# grizzly_bear_jig.net
KiCad netlist of a schematic drawn in EAGLE
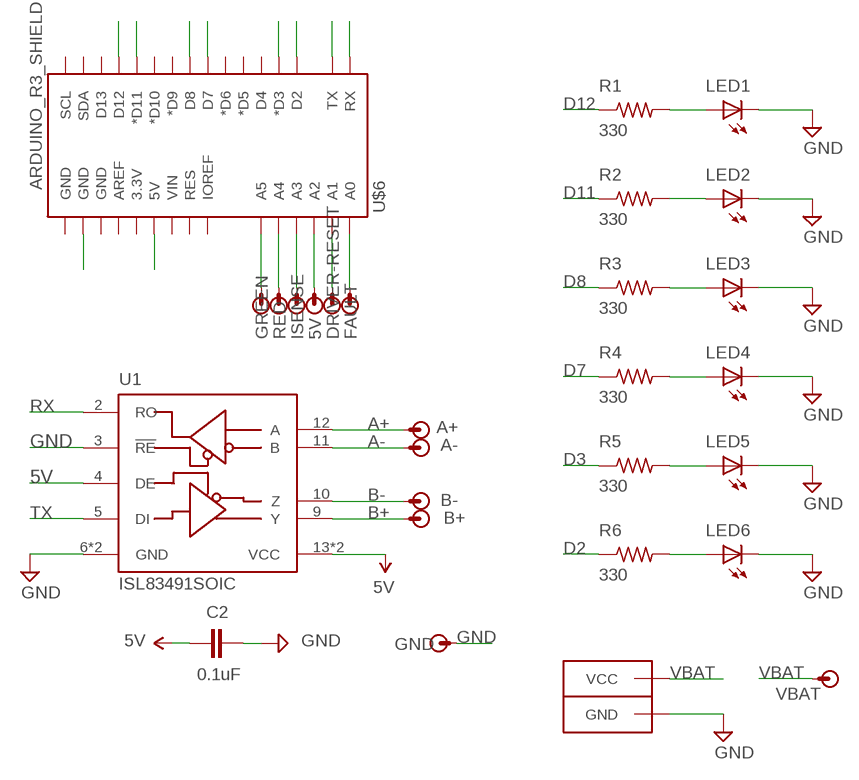
[diagram p0: schematic, sheet 1]

(export (version "E")
  (design (tool "Eeschema 10.0.6"))
  (components
    (comp (ref "5V")
      (value "POGO_PIN")
      (footprint "eagle-import:POGO_PIN_394")
      (libsource (lib "eagle-import") (part "POGO_PIN"))
    )
    (comp (ref "A+")
      (value "POGO_PIN")
      (footprint "eagle-import:POGO_PIN_394")
      (libsource (lib "eagle-import") (part "POGO_PIN"))
    )
    (comp (ref "A-")
      (value "POGO_PIN")
      (footprint "eagle-import:POGO_PIN_394")
      (libsource (lib "eagle-import") (part "POGO_PIN"))
    )
    (comp (ref "B+")
      (value "POGO_PIN")
      (footprint "eagle-import:POGO_PIN_394")
      (libsource (lib "eagle-import") (part "POGO_PIN"))
    )
    (comp (ref "B-")
      (value "POGO_PIN")
      (footprint "eagle-import:POGO_PIN_394")
      (libsource (lib "eagle-import") (part "POGO_PIN"))
    )
    (comp (ref "C2")
      (value "0.1uF")
      (footprint "eagle-import:0603-CAP")
      (libsource (lib "eagle-import") (part "0.1UF-25V(+80/-20%)(0603)"))
    )
    (comp (ref "CONN1")
      (value "ANDERSONHORIZONTAL")
      (footprint "eagle-import:ANDERSON_HORIZONTAL")
      (libsource (lib "eagle-import") (part "ANDERSONHORIZONTAL"))
    )
    (comp (ref "DRIVER-RESET")
      (value "POGO_PIN")
      (footprint "eagle-import:POGO_PIN_394")
      (libsource (lib "eagle-import") (part "POGO_PIN"))
    )
    (comp (ref "FAULT")
      (value "POGO_PIN")
      (footprint "eagle-import:POGO_PIN_394")
      (libsource (lib "eagle-import") (part "POGO_PIN"))
    )
    (comp (ref "GND")
      (value "POGO_PIN")
      (footprint "eagle-import:POGO_PIN_394")
      (libsource (lib "eagle-import") (part "POGO_PIN"))
    )
    (comp (ref "GREEN")
      (value "POGO_PIN")
      (footprint "eagle-import:POGO_PIN_394")
      (libsource (lib "eagle-import") (part "POGO_PIN"))
    )
    (comp (ref "ISENSE")
      (value "POGO_PIN")
      (footprint "eagle-import:POGO_PIN_394")
      (libsource (lib "eagle-import") (part "POGO_PIN"))
    )
    (comp (ref "LED1")
      (value "LED0805")
      (footprint "eagle-import:LED-0805")
      (libsource (lib "eagle-import") (part "LED0805"))
    )
    (comp (ref "LED2")
      (value "LED0805")
      (footprint "eagle-import:LED-0805")
      (libsource (lib "eagle-import") (part "LED0805"))
    )
    (comp (ref "LED3")
      (value "LED0805")
      (footprint "eagle-import:LED-0805")
      (libsource (lib "eagle-import") (part "LED0805"))
    )
    (comp (ref "LED4")
      (value "LED0805")
      (footprint "eagle-import:LED-0805")
      (libsource (lib "eagle-import") (part "LED0805"))
    )
    (comp (ref "LED5")
      (value "LED0805")
      (footprint "eagle-import:LED-0805")
      (libsource (lib "eagle-import") (part "LED0805"))
    )
    (comp (ref "LED6")
      (value "LED0805")
      (footprint "eagle-import:LED-0805")
      (libsource (lib "eagle-import") (part "LED0805"))
    )
    (comp (ref "R1")
      (value "330")
      (footprint "eagle-import:R0603")
      (libsource (lib "eagle-import") (part "R-US_R0603"))
    )
    (comp (ref "R2")
      (value "330")
      (footprint "eagle-import:R0603")
      (libsource (lib "eagle-import") (part "R-US_R0603"))
    )
    (comp (ref "R3")
      (value "330")
      (footprint "eagle-import:R0603")
      (libsource (lib "eagle-import") (part "R-US_R0603"))
    )
    (comp (ref "R4")
      (value "330")
      (footprint "eagle-import:R0603")
      (libsource (lib "eagle-import") (part "R-US_R0603"))
    )
    (comp (ref "R5")
      (value "330")
      (footprint "eagle-import:R0603")
      (libsource (lib "eagle-import") (part "R-US_R0603"))
    )
    (comp (ref "R6")
      (value "330")
      (footprint "eagle-import:R0603")
      (libsource (lib "eagle-import") (part "R-US_R0603"))
    )
    (comp (ref "RED")
      (value "POGO_PIN")
      (footprint "eagle-import:POGO_PIN_394")
      (libsource (lib "eagle-import") (part "POGO_PIN"))
    )
    (comp (ref "U$6")
      (value "ARDUINO_R3_SHIELD")
      (footprint "eagle-import:UNO_R3_SHIELD")
      (libsource (lib "eagle-import") (part "ARDUINO_R3_SHIELD"))
    )
    (comp (ref "U1")
      (value "ISL83491SOIC")
      (footprint "eagle-import:SOIC14")
      (libsource (lib "eagle-import") (part "ISL83491SOIC"))
    )
    (comp (ref "VBAT")
      (value "POGO_PIN")
      (footprint "eagle-import:POGO_PIN_394")
      (libsource (lib "eagle-import") (part "POGO_PIN"))
    )
  )
  (nets
    (net (code "1") (name "/A+") (class "Default")
      (node (ref "A+") (pin "POGO_PIN") (pinfunction "P$1_POGO_PIN") (pintype "bidirectional"))
      (node (ref "U1") (pin "12") (pinfunction "A_12") (pintype "bidirectional"))
    )
    (net (code "2") (name "/A-") (class "Default")
      (node (ref "A-") (pin "POGO_PIN") (pinfunction "P$1_POGO_PIN") (pintype "bidirectional"))
      (node (ref "U1") (pin "11") (pinfunction "B_11") (pintype "bidirectional"))
    )
    (net (code "3") (name "/B+") (class "Default")
      (node (ref "B+") (pin "POGO_PIN") (pinfunction "P$1_POGO_PIN") (pintype "bidirectional"))
      (node (ref "U1") (pin "9") (pinfunction "Y_9") (pintype "bidirectional"))
    )
    (net (code "4") (name "/B-") (class "Default")
      (node (ref "B-") (pin "POGO_PIN") (pinfunction "P$1_POGO_PIN") (pintype "bidirectional"))
      (node (ref "U1") (pin "10") (pinfunction "Z_10") (pintype "bidirectional"))
    )
    (net (code "5") (name "/D2") (class "Default")
      (node (ref "R6") (pin "1") (pinfunction "1_1") (pintype "passive"))
      (node (ref "U$6") (pin "D2") (pinfunction "D2_D2") (pintype "bidirectional"))
    )
    (net (code "6") (name "/D3") (class "Default")
      (node (ref "R5") (pin "1") (pinfunction "1_1") (pintype "passive"))
      (node (ref "U$6") (pin "D3") (pinfunction "*D3_D3") (pintype "bidirectional"))
    )
    (net (code "7") (name "/D7") (class "Default")
      (node (ref "R4") (pin "1") (pinfunction "1_1") (pintype "passive"))
      (node (ref "U$6") (pin "D7") (pinfunction "D7_D7") (pintype "bidirectional"))
    )
    (net (code "8") (name "/D8") (class "Default")
      (node (ref "R3") (pin "1") (pinfunction "1_1") (pintype "passive"))
      (node (ref "U$6") (pin "D8") (pinfunction "D8_D8") (pintype "bidirectional"))
    )
    (net (code "9") (name "/D11") (class "Default")
      (node (ref "R2") (pin "1") (pinfunction "1_1") (pintype "passive"))
      (node (ref "U$6") (pin "D11") (pinfunction "*D11_D11") (pintype "bidirectional"))
    )
    (net (code "10") (name "/D12") (class "Default")
      (node (ref "R1") (pin "1") (pinfunction "1_1") (pintype "passive"))
      (node (ref "U$6") (pin "D12") (pinfunction "D12_D12") (pintype "bidirectional"))
    )
    (net (code "11") (name "/RX") (class "Default")
      (node (ref "U$6") (pin "RX") (pinfunction "RX_RX") (pintype "bidirectional"))
      (node (ref "U1") (pin "2") (pinfunction "RO_2") (pintype "bidirectional"))
    )
    (net (code "12") (name "/TX") (class "Default")
      (node (ref "U$6") (pin "TX") (pinfunction "TX_TX") (pintype "bidirectional"))
      (node (ref "U1") (pin "5") (pinfunction "DI_5") (pintype "bidirectional"))
    )
    (net (code "13") (name "/VBAT") (class "Default")
      (node (ref "CONN1") (pin "PIN2") (pinfunction "VCC_PIN2") (pintype "bidirectional"))
      (node (ref "VBAT") (pin "POGO_PIN") (pinfunction "P$1_POGO_PIN") (pintype "bidirectional"))
    )
    (net (code "14") (name "5V") (class "Default")
      (node (ref "C2") (pin "1") (pinfunction "1_1") (pintype "passive"))
      (node (ref "U$6") (pin "5V") (pinfunction "5V_5V") (pintype "bidirectional"))
      (node (ref "U1") (pin "13") (pinfunction "VCC_13") (pintype "bidirectional"))
      (node (ref "U1") (pin "14") (pinfunction "VCC_14") (pintype "bidirectional"))
      (node (ref "U1") (pin "4") (pinfunction "DE_4") (pintype "bidirectional"))
    )
    (net (code "15") (name "GND") (class "Default")
      (node (ref "C2") (pin "2") (pinfunction "2_2") (pintype "passive"))
      (node (ref "CONN1") (pin "PIN1") (pinfunction "GND_PIN1") (pintype "bidirectional"))
      (node (ref "GND") (pin "POGO_PIN") (pinfunction "P$1_POGO_PIN") (pintype "bidirectional"))
      (node (ref "LED1") (pin "C") (pinfunction "C_C") (pintype "passive"))
      (node (ref "LED2") (pin "C") (pinfunction "C_C") (pintype "passive"))
      (node (ref "LED3") (pin "C") (pinfunction "C_C") (pintype "passive"))
      (node (ref "LED4") (pin "C") (pinfunction "C_C") (pintype "passive"))
      (node (ref "LED5") (pin "C") (pinfunction "C_C") (pintype "passive"))
      (node (ref "LED6") (pin "C") (pinfunction "C_C") (pintype "passive"))
      (node (ref "U$6") (pin "GND@1") (pinfunction "GND_GND@1") (pintype "bidirectional"))
      (node (ref "U1") (pin "3") (pinfunction "~{RE}_3") (pintype "bidirectional"))
      (node (ref "U1") (pin "6") (pinfunction "GND_6") (pintype "bidirectional"))
      (node (ref "U1") (pin "7") (pinfunction "GND_7") (pintype "bidirectional"))
    )
    (net (code "16") (name "Net-(5V-P$1)") (class "Default")
      (node (ref "5V") (pin "POGO_PIN") (pinfunction "P$1_POGO_PIN") (pintype "bidirectional"))
      (node (ref "U$6") (pin "A2") (pinfunction "A2_A2") (pintype "bidirectional"))
    )
    (net (code "17") (name "Net-(DRIVER-RESET-P$1)") (class "Default")
      (node (ref "DRIVER-RESET") (pin "POGO_PIN") (pinfunction "P$1_POGO_PIN") (pintype "bidirectional"))
      (node (ref "U$6") (pin "A1") (pinfunction "A1_A1") (pintype "bidirectional"))
    )
    (net (code "18") (name "Net-(FAULT-P$1)") (class "Default")
      (node (ref "FAULT") (pin "POGO_PIN") (pinfunction "P$1_POGO_PIN") (pintype "bidirectional"))
      (node (ref "U$6") (pin "A0") (pinfunction "A0_A0") (pintype "bidirectional"))
    )
    (net (code "19") (name "Net-(GREEN-P$1)") (class "Default")
      (node (ref "GREEN") (pin "POGO_PIN") (pinfunction "P$1_POGO_PIN") (pintype "bidirectional"))
      (node (ref "U$6") (pin "A5") (pinfunction "A5_A5") (pintype "bidirectional"))
    )
    (net (code "20") (name "Net-(ISENSE-P$1)") (class "Default")
      (node (ref "ISENSE") (pin "POGO_PIN") (pinfunction "P$1_POGO_PIN") (pintype "bidirectional"))
      (node (ref "U$6") (pin "A3") (pinfunction "A3_A3") (pintype "bidirectional"))
    )
    (net (code "21") (name "Net-(LED1-PadA)") (class "Default")
      (node (ref "LED1") (pin "A") (pinfunction "A_A") (pintype "passive"))
      (node (ref "R1") (pin "2") (pinfunction "2_2") (pintype "passive"))
    )
    (net (code "22") (name "Net-(LED2-PadA)") (class "Default")
      (node (ref "LED2") (pin "A") (pinfunction "A_A") (pintype "passive"))
      (node (ref "R2") (pin "2") (pinfunction "2_2") (pintype "passive"))
    )
    (net (code "23") (name "Net-(LED3-PadA)") (class "Default")
      (node (ref "LED3") (pin "A") (pinfunction "A_A") (pintype "passive"))
      (node (ref "R3") (pin "2") (pinfunction "2_2") (pintype "passive"))
    )
    (net (code "24") (name "Net-(LED4-PadA)") (class "Default")
      (node (ref "LED4") (pin "A") (pinfunction "A_A") (pintype "passive"))
      (node (ref "R4") (pin "2") (pinfunction "2_2") (pintype "passive"))
    )
    (net (code "25") (name "Net-(LED5-PadA)") (class "Default")
      (node (ref "LED5") (pin "A") (pinfunction "A_A") (pintype "passive"))
      (node (ref "R5") (pin "2") (pinfunction "2_2") (pintype "passive"))
    )
    (net (code "26") (name "Net-(LED6-PadA)") (class "Default")
      (node (ref "LED6") (pin "A") (pinfunction "A_A") (pintype "passive"))
      (node (ref "R6") (pin "2") (pinfunction "2_2") (pintype "passive"))
    )
    (net (code "27") (name "Net-(RED-P$1)") (class "Default")
      (node (ref "RED") (pin "POGO_PIN") (pinfunction "P$1_POGO_PIN") (pintype "bidirectional"))
      (node (ref "U$6") (pin "A4") (pinfunction "A4_A4") (pintype "bidirectional"))
    )
    (net (code "28") (name "unconnected-(U$6-*D5-PadD5)") (class "Default")
      (node (ref "U$6") (pin "D5") (pinfunction "*D5_D5") (pintype "bidirectional"))
    )
    (net (code "29") (name "unconnected-(U$6-*D6-PadD6)") (class "Default")
      (node (ref "U$6") (pin "D6") (pinfunction "*D6_D6") (pintype "bidirectional"))
    )
    (net (code "30") (name "unconnected-(U$6-*D9-PadD9)") (class "Default")
      (node (ref "U$6") (pin "D9") (pinfunction "*D9_D9") (pintype "bidirectional"))
    )
    (net (code "31") (name "unconnected-(U$6-*D10-PadD10)") (class "Default")
      (node (ref "U$6") (pin "D10") (pinfunction "*D10_D10") (pintype "bidirectional"))
    )
    (net (code "32") (name "unconnected-(U$6-GND-PadGND@0)") (class "Default")
      (node (ref "U$6") (pin "GND@0") (pinfunction "GND_GND@0") (pintype "bidirectional"))
    )
    (net (code "33") (name "unconnected-(U$6-GND-PadGND@2)") (class "Default")
      (node (ref "U$6") (pin "GND@2") (pinfunction "GND_GND@2") (pintype "bidirectional"))
    )
    (net (code "34") (name "unconnected-(U$6-Pad3.3V)") (class "Default")
      (node (ref "U$6") (pin "3.3V") (pinfunction "3.3V_3.3V") (pintype "bidirectional"))
    )
    (net (code "35") (name "unconnected-(U$6-PadAREF)") (class "Default")
      (node (ref "U$6") (pin "AREF") (pinfunction "AREF_AREF") (pintype "bidirectional"))
    )
    (net (code "36") (name "unconnected-(U$6-PadD4)") (class "Default")
      (node (ref "U$6") (pin "D4") (pinfunction "D4_D4") (pintype "bidirectional"))
    )
    (net (code "37") (name "unconnected-(U$6-PadD13)") (class "Default")
      (node (ref "U$6") (pin "D13") (pinfunction "D13_D13") (pintype "bidirectional"))
    )
    (net (code "38") (name "unconnected-(U$6-PadIOREF)") (class "Default")
      (node (ref "U$6") (pin "IOREF") (pinfunction "IOREF_IOREF") (pintype "bidirectional"))
    )
    (net (code "39") (name "unconnected-(U$6-PadRES)") (class "Default")
      (node (ref "U$6") (pin "RES") (pinfunction "RES_RES") (pintype "bidirectional"))
    )
    (net (code "40") (name "unconnected-(U$6-PadSCL)") (class "Default")
      (node (ref "U$6") (pin "SCL") (pinfunction "SCL_SCL") (pintype "bidirectional"))
    )
    (net (code "41") (name "unconnected-(U$6-PadSDA)") (class "Default")
      (node (ref "U$6") (pin "SDA") (pinfunction "SDA_SDA") (pintype "bidirectional"))
    )
    (net (code "42") (name "unconnected-(U$6-PadVIN)") (class "Default")
      (node (ref "U$6") (pin "VIN") (pinfunction "VIN_VIN") (pintype "bidirectional"))
    )
  )
)
